# Telemetry_temp_meas.net
KiCad netlist of a schematic drawn in Altium Designer
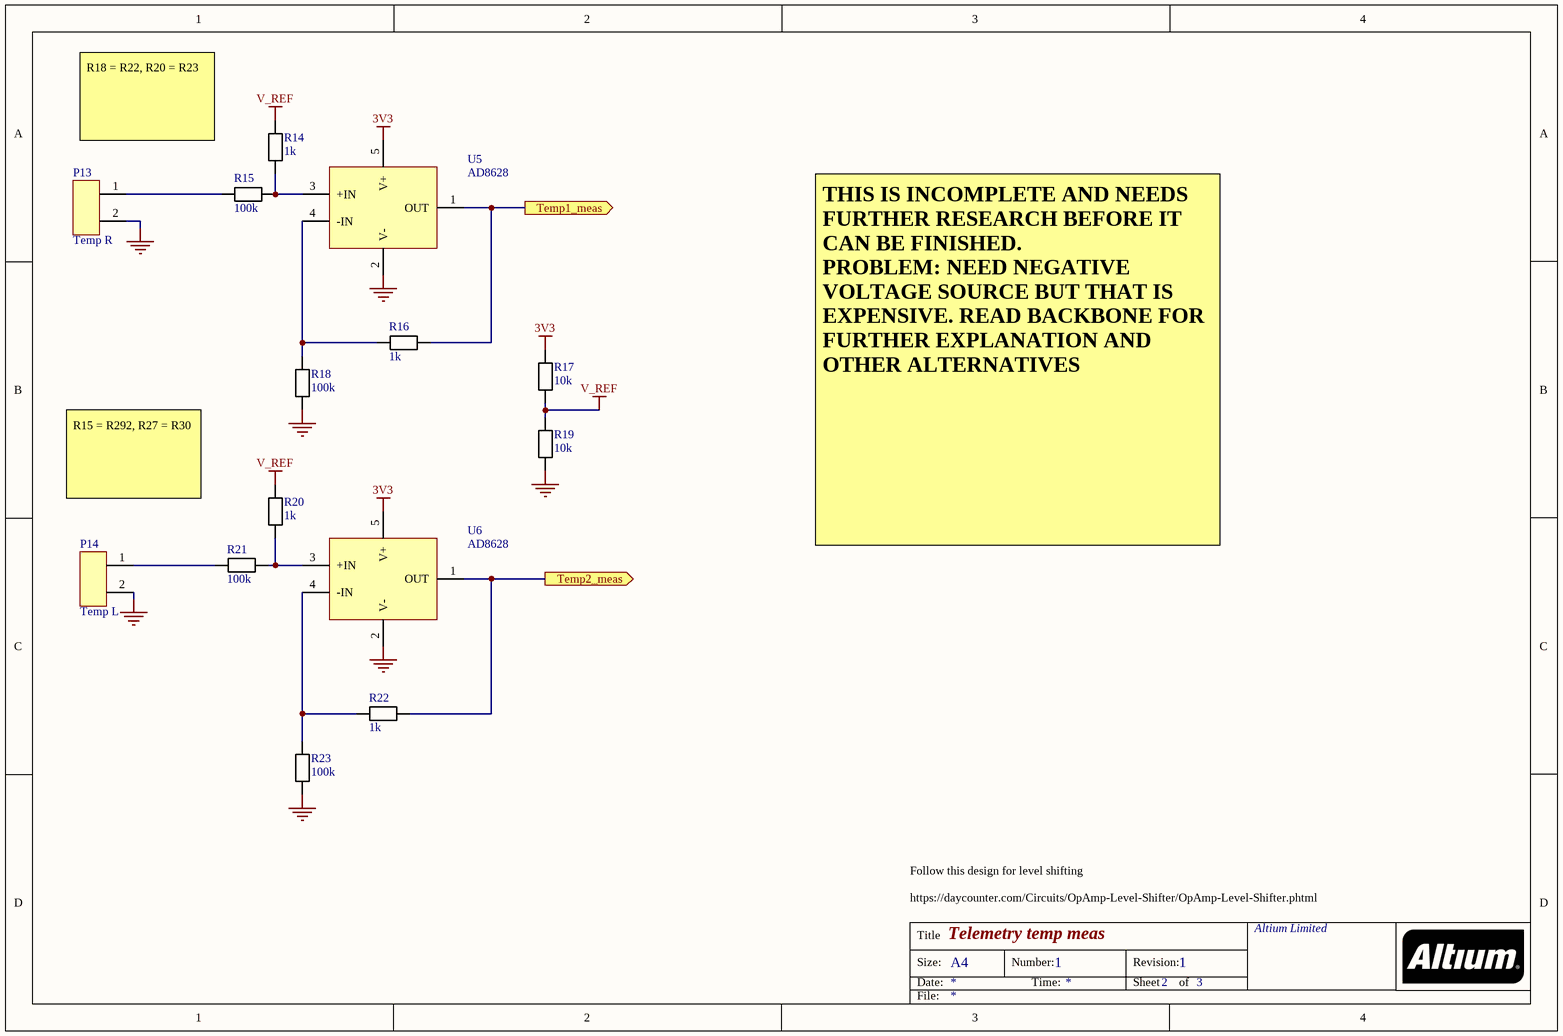
[diagram p0: Telemetry_temp_meas.SchDoc]

(export (version "E")
  (design (tool "Eeschema 10.0.6"))
  (components
    (comp (ref "P13")
      (value "Temp R")
      (footprint "JST_SE_2PIN")
      (libsource (lib "FF_component_lib") (part "JST_SE_2PIN"))
    )
    (comp (ref "P14")
      (value "Temp L")
      (footprint "JST_SE_2PIN")
      (libsource (lib "FF_component_lib") (part "JST_SE_2PIN"))
    )
    (comp (ref "R14")
      (value "1k")
      (footprint "R_SMD_0805_pcb")
      (fields (field (name "Comment") "SMD"))
      (libsource (lib "FF_component_lib") (part "R_SMD_0805"))
    )
    (comp (ref "R15")
      (value "100k")
      (footprint "R_SMD_0805_pcb")
      (fields (field (name "Comment") "SMD"))
      (libsource (lib "FF_component_lib") (part "R_SMD_0805"))
    )
    (comp (ref "R16")
      (value "1k")
      (footprint "R_SMD_0805_pcb")
      (fields (field (name "Comment") "SMD"))
      (libsource (lib "FF_component_lib") (part "R_SMD_0805"))
    )
    (comp (ref "R17")
      (value "10k")
      (footprint "R_SMD_0805_pcb")
      (fields (field (name "Comment") "SMD"))
      (libsource (lib "FF_component_lib") (part "R_SMD_0805"))
    )
    (comp (ref "R18")
      (value "100k")
      (footprint "R_SMD_0805_pcb")
      (fields (field (name "Comment") "SMD"))
      (libsource (lib "FF_component_lib") (part "R_SMD_0805"))
    )
    (comp (ref "R19")
      (value "10k")
      (footprint "R_SMD_0805_pcb")
      (fields (field (name "Comment") "SMD"))
      (libsource (lib "FF_component_lib") (part "R_SMD_0805"))
    )
    (comp (ref "R20")
      (value "1k")
      (footprint "R_SMD_0805_pcb")
      (fields (field (name "Comment") "SMD"))
      (libsource (lib "FF_component_lib") (part "R_SMD_0805"))
    )
    (comp (ref "R21")
      (value "100k")
      (footprint "R_SMD_0805_pcb")
      (fields (field (name "Comment") "SMD"))
      (libsource (lib "FF_component_lib") (part "R_SMD_0805"))
    )
    (comp (ref "R22")
      (value "1k")
      (footprint "R_SMD_0805_pcb")
      (fields (field (name "Comment") "SMD"))
      (libsource (lib "FF_component_lib") (part "R_SMD_0805"))
    )
    (comp (ref "R23")
      (value "100k")
      (footprint "R_SMD_0805_pcb")
      (fields (field (name "Comment") "SMD"))
      (libsource (lib "FF_component_lib") (part "R_SMD_0805"))
    )
    (comp (ref "U5")
      (value "AD8628")
      (footprint "SOT-23-5")
      (libsource (lib "FF_component_lib") (part "AD8628WAUJZ-R7_SOT-23-5"))
    )
    (comp (ref "U6")
      (value "AD8628")
      (footprint "SOT-23-5")
      (libsource (lib "FF_component_lib") (part "AD8628WAUJZ-R7_SOT-23-5"))
    )
  )
  (nets
    (net (code "1") (name "/Temp1_meas") (class "Default")
      (node (ref "R16") (pin "2") (pinfunction "2_2") (pintype "passive"))
      (node (ref "U5") (pin "1") (pinfunction "OUT_1") (pintype "passive"))
    )
    (net (code "2") (name "/Temp2_meas") (class "Default")
      (node (ref "R22") (pin "2") (pinfunction "2_2") (pintype "passive"))
      (node (ref "U6") (pin "1") (pinfunction "OUT_1") (pintype "passive"))
    )
    (net (code "3") (name "3V3") (class "Default")
      (node (ref "R17") (pin "2") (pinfunction "2_2") (pintype "passive"))
      (node (ref "U5") (pin "5") (pinfunction "V+_5") (pintype "passive"))
      (node (ref "U6") (pin "5") (pinfunction "V+_5") (pintype "passive"))
    )
    (net (code "4") (name "GND") (class "Default")
      (node (ref "P13") (pin "2") (pinfunction "2_2") (pintype "passive"))
      (node (ref "P14") (pin "2") (pinfunction "2_2") (pintype "passive"))
      (node (ref "R18") (pin "1") (pinfunction "1_1") (pintype "passive"))
      (node (ref "R19") (pin "1") (pinfunction "1_1") (pintype "passive"))
      (node (ref "R23") (pin "2") (pinfunction "2_2") (pintype "passive"))
      (node (ref "U5") (pin "2") (pinfunction "V-_2") (pintype "passive"))
      (node (ref "U6") (pin "2") (pinfunction "V-_2") (pintype "passive"))
    )
    (net (code "5") (name "Net-(P13-Pad1)") (class "Default")
      (node (ref "P13") (pin "1") (pinfunction "1_1") (pintype "passive"))
      (node (ref "R15") (pin "1") (pinfunction "1_1") (pintype "passive"))
    )
    (net (code "6") (name "Net-(P14-Pad1)") (class "Default")
      (node (ref "P14") (pin "1") (pinfunction "1_1") (pintype "passive"))
      (node (ref "R21") (pin "1") (pinfunction "1_1") (pintype "passive"))
    )
    (net (code "7") (name "Net-(U5-+IN)") (class "Default")
      (node (ref "R14") (pin "1") (pinfunction "1_1") (pintype "passive"))
      (node (ref "R15") (pin "2") (pinfunction "2_2") (pintype "passive"))
      (node (ref "U5") (pin "3") (pinfunction "+IN_3") (pintype "passive"))
    )
    (net (code "8") (name "Net-(U5--IN)") (class "Default")
      (node (ref "R16") (pin "1") (pinfunction "1_1") (pintype "passive"))
      (node (ref "R18") (pin "2") (pinfunction "2_2") (pintype "passive"))
      (node (ref "U5") (pin "4") (pinfunction "-IN_4") (pintype "passive"))
    )
    (net (code "9") (name "Net-(U6-+IN)") (class "Default")
      (node (ref "R20") (pin "1") (pinfunction "1_1") (pintype "passive"))
      (node (ref "R21") (pin "2") (pinfunction "2_2") (pintype "passive"))
      (node (ref "U6") (pin "3") (pinfunction "+IN_3") (pintype "passive"))
    )
    (net (code "10") (name "Net-(U6--IN)") (class "Default")
      (node (ref "R22") (pin "1") (pinfunction "1_1") (pintype "passive"))
      (node (ref "R23") (pin "1") (pinfunction "1_1") (pintype "passive"))
      (node (ref "U6") (pin "4") (pinfunction "-IN_4") (pintype "passive"))
    )
    (net (code "11") (name "V_REF") (class "Default")
      (node (ref "R14") (pin "2") (pinfunction "2_2") (pintype "passive"))
      (node (ref "R17") (pin "1") (pinfunction "1_1") (pintype "passive"))
      (node (ref "R19") (pin "2") (pinfunction "2_2") (pintype "passive"))
      (node (ref "R20") (pin "2") (pinfunction "2_2") (pintype "passive"))
    )
  )
)
